# combo_-_no_usb_-_pth_-_tcrt5000.net
KiCad netlist of a schematic drawn in EAGLE
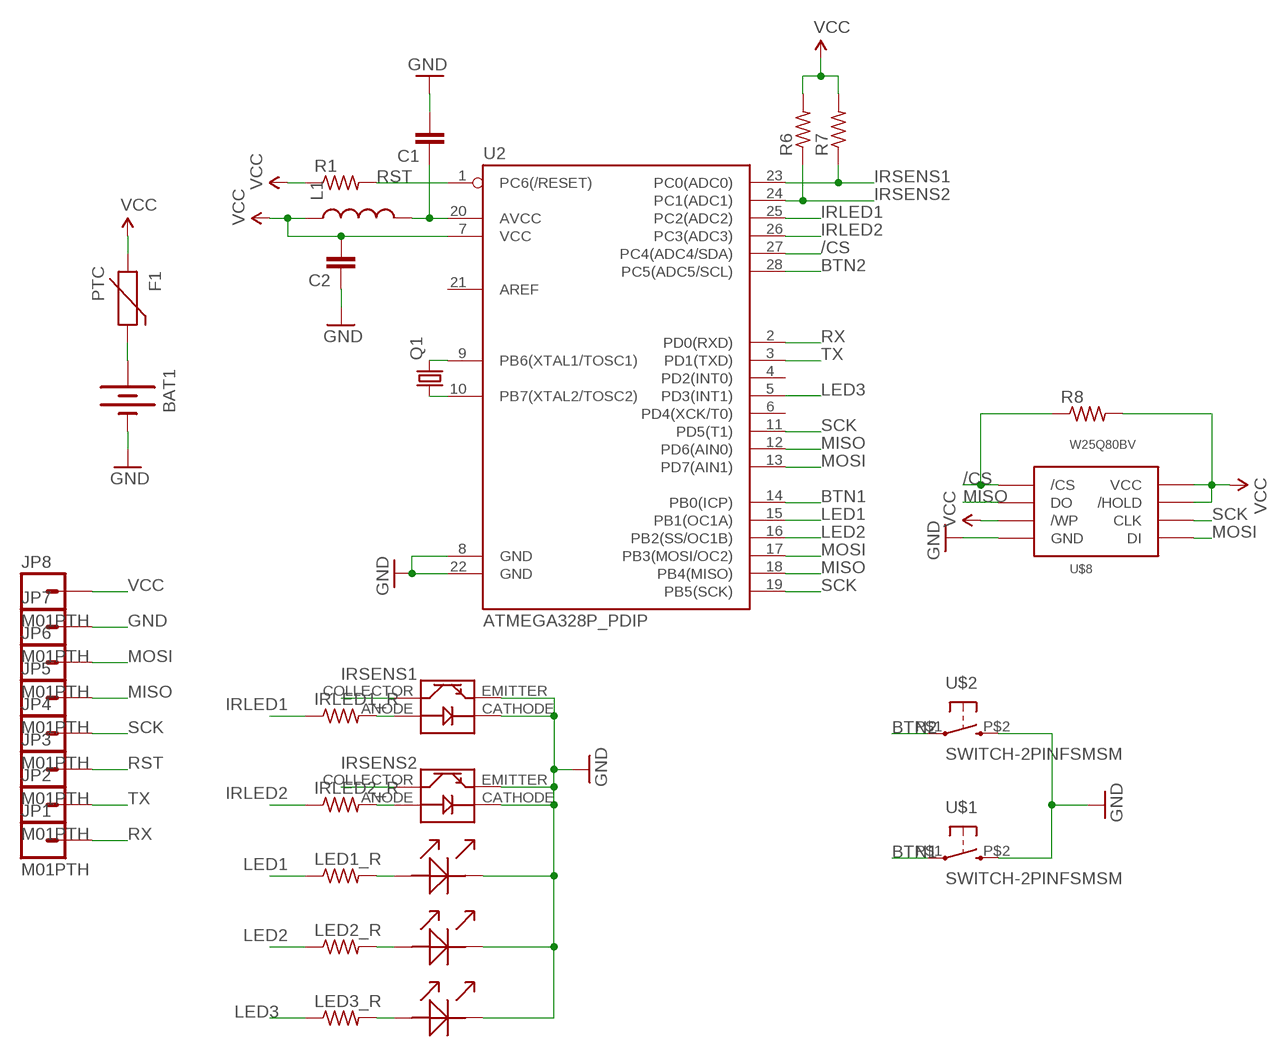
[diagram p0: schematic, sheet 1]

(export (version "E")
  (design (tool "Eeschema 10.0.6"))
  (components
    (comp (ref "BAT1")
      (value "BATTERYBA2032SM")
      (footprint "eagle-import:BA2032SM")
      (libsource (lib "eagle-import") (part "BATTERYBA2032SM"))
    )
    (comp (ref "C1")
      (value "CAP0805")
      (footprint "eagle-import:0805")
      (libsource (lib "eagle-import") (part "CAP0805"))
    )
    (comp (ref "C2")
      (value "CAP0805")
      (footprint "eagle-import:0805")
      (libsource (lib "eagle-import") (part "CAP0805"))
    )
    (comp (ref "F1")
      (value "PTC")
      (footprint "eagle-import:R0805")
      (libsource (lib "eagle-import") (part "PTC"))
    )
    (comp (ref "IRLED1_R")
      (value "R-US_M0805")
      (footprint "eagle-import:M0805")
      (libsource (lib "eagle-import") (part "R-US_M0805"))
    )
    (comp (ref "IRLED2_R")
      (value "R-US_M0805")
      (footprint "eagle-import:M0805")
      (libsource (lib "eagle-import") (part "R-US_M0805"))
    )
    (comp (ref "JP1")
      (value "M01PTH")
      (footprint "eagle-import:1X01")
      (libsource (lib "eagle-import") (part "M01PTH"))
    )
    (comp (ref "JP2")
      (value "M01PTH")
      (footprint "eagle-import:1X01")
      (libsource (lib "eagle-import") (part "M01PTH"))
    )
    (comp (ref "JP3")
      (value "M01PTH")
      (footprint "eagle-import:1X01")
      (libsource (lib "eagle-import") (part "M01PTH"))
    )
    (comp (ref "JP4")
      (value "M01PTH")
      (footprint "eagle-import:1X01")
      (libsource (lib "eagle-import") (part "M01PTH"))
    )
    (comp (ref "JP5")
      (value "M01PTH")
      (footprint "eagle-import:1X01")
      (libsource (lib "eagle-import") (part "M01PTH"))
    )
    (comp (ref "JP6")
      (value "M01PTH")
      (footprint "eagle-import:1X01")
      (libsource (lib "eagle-import") (part "M01PTH"))
    )
    (comp (ref "JP7")
      (value "M01PTH")
      (footprint "eagle-import:1X01")
      (libsource (lib "eagle-import") (part "M01PTH"))
    )
    (comp (ref "JP8")
      (value "M01PTH")
      (footprint "eagle-import:1X01")
      (libsource (lib "eagle-import") (part "M01PTH"))
    )
    (comp (ref "L1")
      (value "INDUCTOR0805")
      (footprint "eagle-import:0805")
      (libsource (lib "eagle-import") (part "INDUCTOR0805"))
    )
    (comp (ref "LED1_R")
      (value "R-US_M0805")
      (footprint "eagle-import:M0805")
      (libsource (lib "eagle-import") (part "R-US_M0805"))
    )
    (comp (ref "LED2_R")
      (value "R-US_M0805")
      (footprint "eagle-import:M0805")
      (libsource (lib "eagle-import") (part "R-US_M0805"))
    )
    (comp (ref "LED3_R")
      (value "R-US_M0805")
      (footprint "eagle-import:M0805")
      (libsource (lib "eagle-import") (part "R-US_M0805"))
    )
    (comp (ref "Q1")
      (value "CRYSTALTC26V")
      (footprint "eagle-import:TC26V")
      (libsource (lib "eagle-import") (part "CRYSTALTC26V"))
    )
    (comp (ref "R1")
      (value "R-US_M0805")
      (footprint "eagle-import:M0805")
      (libsource (lib "eagle-import") (part "R-US_M0805"))
    )
    (comp (ref "R6")
      (value "R-US_M0805")
      (footprint "eagle-import:M0805")
      (libsource (lib "eagle-import") (part "R-US_M0805"))
    )
    (comp (ref "R7")
      (value "R-US_M0805")
      (footprint "eagle-import:M0805")
      (libsource (lib "eagle-import") (part "R-US_M0805"))
    )
    (comp (ref "R8")
      (value "R-US_M0805")
      (footprint "eagle-import:M0805")
      (libsource (lib "eagle-import") (part "R-US_M0805"))
    )
    (comp (ref "U$1")
      (value "SWITCH-2PINFSMSM")
      (footprint "eagle-import:FSMSM-BUTTON")
      (libsource (lib "eagle-import") (part "SWITCH-2PINFSMSM"))
    )
    (comp (ref "U$2")
      (value "SWITCH-2PINFSMSM")
      (footprint "eagle-import:FSMSM-BUTTON")
      (libsource (lib "eagle-import") (part "SWITCH-2PINFSMSM"))
    )
    (comp (ref "U$3")
      (value "IR_SENSORTCRT5000")
      (footprint "eagle-import:TCRT5000")
      (libsource (lib "eagle-import") (part "IR_SENSORTCRT5000"))
    )
    (comp (ref "U$4")
      (value "IR_SENSORTCRT5000")
      (footprint "eagle-import:TCRT5000")
      (libsource (lib "eagle-import") (part "IR_SENSORTCRT5000"))
    )
    (comp (ref "U$5")
      (value "LEDPTH")
      (footprint "eagle-import:LED")
      (libsource (lib "eagle-import") (part "LEDPTH"))
    )
    (comp (ref "U$6")
      (value "LEDPTH")
      (footprint "eagle-import:LED")
      (libsource (lib "eagle-import") (part "LEDPTH"))
    )
    (comp (ref "U$7")
      (value "LED0603")
      (footprint "eagle-import:0603")
      (libsource (lib "eagle-import") (part "LED0603"))
    )
    (comp (ref "U$8")
      (value "W25Q80BVSOIC-08")
      (footprint "eagle-import:W25Q80BV-SOIC-208MIL")
      (libsource (lib "eagle-import") (part "W25Q80BVSOIC-08"))
    )
    (comp (ref "U2")
      (value "ATMEGA328P_PDIP")
      (footprint "eagle-import:DIL28-3")
      (libsource (lib "eagle-import") (part "ATMEGA328P_PDIP"))
    )
  )
  (nets
    (net (code "1") (name "/BTN1") (class "Default")
      (node (ref "U$1") (pin "P$1") (pinfunction "1_P$1") (pintype "passive"))
      (node (ref "U2") (pin "14") (pinfunction "PB0(ICP)_14") (pintype "bidirectional"))
    )
    (net (code "2") (name "/BTN2") (class "Default")
      (node (ref "U$2") (pin "P$1") (pinfunction "1_P$1") (pintype "passive"))
      (node (ref "U2") (pin "28") (pinfunction "PC5(ADC5/SCL)_28") (pintype "bidirectional"))
    )
    (net (code "3") (name "/IRLED1") (class "Default")
      (node (ref "IRLED1_R") (pin "1") (pinfunction "1_1") (pintype "passive"))
      (node (ref "U2") (pin "25") (pinfunction "PC2(ADC2)_25") (pintype "bidirectional"))
    )
    (net (code "4") (name "/IRLED2") (class "Default")
      (node (ref "IRLED2_R") (pin "1") (pinfunction "1_1") (pintype "passive"))
      (node (ref "U2") (pin "26") (pinfunction "PC3(ADC3)_26") (pintype "bidirectional"))
    )
    (net (code "5") (name "/IRSENS1") (class "Default")
      (node (ref "R7") (pin "1") (pinfunction "1_1") (pintype "passive"))
      (node (ref "U$3") (pin "COLLECTOR") (pinfunction "COLLECTOR_COLLECTOR") (pintype "input"))
      (node (ref "U2") (pin "23") (pinfunction "PC0(ADC0)_23") (pintype "bidirectional"))
    )
    (net (code "6") (name "/IRSENS2") (class "Default")
      (node (ref "R6") (pin "1") (pinfunction "1_1") (pintype "passive"))
      (node (ref "U$4") (pin "COLLECTOR") (pinfunction "COLLECTOR_COLLECTOR") (pintype "input"))
      (node (ref "U2") (pin "24") (pinfunction "PC1(ADC1)_24") (pintype "bidirectional"))
    )
    (net (code "7") (name "/LED1") (class "Default")
      (node (ref "LED1_R") (pin "1") (pinfunction "1_1") (pintype "passive"))
      (node (ref "U2") (pin "15") (pinfunction "PB1(OC1A)_15") (pintype "bidirectional"))
    )
    (net (code "8") (name "/LED2") (class "Default")
      (node (ref "LED2_R") (pin "1") (pinfunction "1_1") (pintype "passive"))
      (node (ref "U2") (pin "16") (pinfunction "PB2(SS/OC1B)_16") (pintype "bidirectional"))
    )
    (net (code "9") (name "/LED3") (class "Default")
      (node (ref "LED3_R") (pin "1") (pinfunction "1_1") (pintype "passive"))
      (node (ref "U2") (pin "5") (pinfunction "PD3(INT1)_5") (pintype "bidirectional"))
    )
    (net (code "10") (name "/MISO") (class "Default")
      (node (ref "JP5") (pin "1") (pinfunction "1_1") (pintype "passive"))
      (node (ref "U$8") (pin "DO") (pinfunction "DO_DO") (pintype "bidirectional"))
      (node (ref "U2") (pin "12") (pinfunction "PD6(AIN0)_12") (pintype "bidirectional"))
      (node (ref "U2") (pin "18") (pinfunction "PB4(MISO)_18") (pintype "bidirectional"))
    )
    (net (code "11") (name "/MOSI") (class "Default")
      (node (ref "JP6") (pin "1") (pinfunction "1_1") (pintype "passive"))
      (node (ref "U$8") (pin "DI") (pinfunction "DI_DI") (pintype "bidirectional"))
      (node (ref "U2") (pin "13") (pinfunction "PD7(AIN1)_13") (pintype "bidirectional"))
      (node (ref "U2") (pin "17") (pinfunction "PB3(MOSI/OC2)_17") (pintype "bidirectional"))
    )
    (net (code "12") (name "/RST") (class "Default")
      (node (ref "JP3") (pin "1") (pinfunction "1_1") (pintype "passive"))
      (node (ref "R1") (pin "2") (pinfunction "2_2") (pintype "passive"))
      (node (ref "U2") (pin "1") (pinfunction "PC6(/RESET)_1") (pintype "bidirectional"))
    )
    (net (code "13") (name "/RX") (class "Default")
      (node (ref "JP1") (pin "1") (pinfunction "1_1") (pintype "passive"))
      (node (ref "U2") (pin "2") (pinfunction "PD0(RXD)_2") (pintype "bidirectional"))
    )
    (net (code "14") (name "/SCK") (class "Default")
      (node (ref "JP4") (pin "1") (pinfunction "1_1") (pintype "passive"))
      (node (ref "U$8") (pin "CLK") (pinfunction "CLK_CLK") (pintype "input"))
      (node (ref "U2") (pin "11") (pinfunction "PD5(T1)_11") (pintype "bidirectional"))
      (node (ref "U2") (pin "19") (pinfunction "PB5(SCK)_19") (pintype "bidirectional"))
    )
    (net (code "15") (name "/TX") (class "Default")
      (node (ref "JP2") (pin "1") (pinfunction "1_1") (pintype "passive"))
      (node (ref "U2") (pin "3") (pinfunction "PD1(TXD)_3") (pintype "bidirectional"))
    )
    (net (code "16") (name "/{slash}CS") (class "Default")
      (node (ref "R8") (pin "1") (pinfunction "1_1") (pintype "passive"))
      (node (ref "U$8") (pin "/CS") (pinfunction "/CS_/CS") (pintype "input"))
      (node (ref "U2") (pin "27") (pinfunction "PC4(ADC4/SDA)_27") (pintype "bidirectional"))
    )
    (net (code "17") (name "GND") (class "Default")
      (node (ref "BAT1") (pin "-") (pinfunction "-_-") (pintype "power_in"))
      (node (ref "C1") (pin "2") (pinfunction "2_2") (pintype "passive"))
      (node (ref "C2") (pin "1") (pinfunction "1_1") (pintype "passive"))
      (node (ref "JP7") (pin "1") (pinfunction "1_1") (pintype "passive"))
      (node (ref "U$1") (pin "P$2") (pinfunction "3_P$2") (pintype "passive"))
      (node (ref "U$2") (pin "P$2") (pinfunction "3_P$2") (pintype "passive"))
      (node (ref "U$3") (pin "CATHODE") (pinfunction "LED-_CATHODE") (pintype "input"))
      (node (ref "U$3") (pin "EMITTER") (pinfunction "EMITTER_EMITTER") (pintype "input"))
      (node (ref "U$4") (pin "CATHODE") (pinfunction "LED-_CATHODE") (pintype "input"))
      (node (ref "U$4") (pin "EMITTER") (pinfunction "EMITTER_EMITTER") (pintype "input"))
      (node (ref "U$5") (pin "-") (pinfunction "-_-") (pintype "bidirectional"))
      (node (ref "U$6") (pin "-") (pinfunction "-_-") (pintype "bidirectional"))
      (node (ref "U$7") (pin "2") (pinfunction "-_2") (pintype "bidirectional"))
      (node (ref "U$8") (pin "GND") (pinfunction "GND_GND") (pintype "power_in"))
      (node (ref "U2") (pin "22") (pinfunction "GND_22") (pintype "bidirectional"))
      (node (ref "U2") (pin "8") (pinfunction "GND_8") (pintype "bidirectional"))
    )
    (net (code "18") (name "Net-(BAT1-Pad+)") (class "Default")
      (node (ref "BAT1") (pin "+") (pinfunction "+_+") (pintype "power_in"))
      (node (ref "F1") (pin "2") (pinfunction "2_2") (pintype "bidirectional"))
    )
    (net (code "19") (name "Net-(LED1_R-Pad2)") (class "Default")
      (node (ref "LED1_R") (pin "2") (pinfunction "2_2") (pintype "passive"))
      (node (ref "U$5") (pin "+") (pinfunction "+_+") (pintype "bidirectional"))
    )
    (net (code "20") (name "Net-(LED2_R-Pad2)") (class "Default")
      (node (ref "LED2_R") (pin "2") (pinfunction "2_2") (pintype "passive"))
      (node (ref "U$6") (pin "+") (pinfunction "+_+") (pintype "bidirectional"))
    )
    (net (code "21") (name "Net-(U$3-LED+)") (class "Default")
      (node (ref "IRLED1_R") (pin "2") (pinfunction "2_2") (pintype "passive"))
      (node (ref "U$3") (pin "ANODE") (pinfunction "LED+_ANODE") (pintype "input"))
    )
    (net (code "22") (name "Net-(U$4-LED+)") (class "Default")
      (node (ref "IRLED2_R") (pin "2") (pinfunction "2_2") (pintype "passive"))
      (node (ref "U$4") (pin "ANODE") (pinfunction "LED+_ANODE") (pintype "input"))
    )
    (net (code "23") (name "Net-(U$7-+)") (class "Default")
      (node (ref "LED3_R") (pin "2") (pinfunction "2_2") (pintype "passive"))
      (node (ref "U$7") (pin "1") (pinfunction "+_1") (pintype "bidirectional"))
    )
    (net (code "24") (name "Net-(U2-AVCC)") (class "Default")
      (node (ref "C1") (pin "1") (pinfunction "1_1") (pintype "passive"))
      (node (ref "L1") (pin "2") (pinfunction "2_2") (pintype "passive"))
      (node (ref "U2") (pin "20") (pinfunction "AVCC_20") (pintype "bidirectional"))
    )
    (net (code "25") (name "Net-(U2-PB6(XTAL1{slash}TOSC1))") (class "Default")
      (node (ref "Q1") (pin "2") (pinfunction "2_2") (pintype "passive"))
      (node (ref "U2") (pin "9") (pinfunction "PB6(XTAL1/TOSC1)_9") (pintype "bidirectional"))
    )
    (net (code "26") (name "Net-(U2-PB7(XTAL2{slash}TOSC2))") (class "Default")
      (node (ref "Q1") (pin "1") (pinfunction "1_1") (pintype "passive"))
      (node (ref "U2") (pin "10") (pinfunction "PB7(XTAL2/TOSC2)_10") (pintype "bidirectional"))
    )
    (net (code "27") (name "VCC") (class "Default")
      (node (ref "C2") (pin "2") (pinfunction "2_2") (pintype "passive"))
      (node (ref "F1") (pin "1") (pinfunction "1_1") (pintype "bidirectional"))
      (node (ref "JP8") (pin "1") (pinfunction "1_1") (pintype "passive"))
      (node (ref "L1") (pin "1") (pinfunction "1_1") (pintype "passive"))
      (node (ref "R1") (pin "1") (pinfunction "1_1") (pintype "passive"))
      (node (ref "R6") (pin "2") (pinfunction "2_2") (pintype "passive"))
      (node (ref "R7") (pin "2") (pinfunction "2_2") (pintype "passive"))
      (node (ref "R8") (pin "2") (pinfunction "2_2") (pintype "passive"))
      (node (ref "U$8") (pin "/HOLD") (pinfunction "/HOLD_/HOLD") (pintype "bidirectional"))
      (node (ref "U$8") (pin "/WP") (pinfunction "/WP_/WP") (pintype "bidirectional"))
      (node (ref "U$8") (pin "VCC") (pinfunction "VCC_VCC") (pintype "power_in"))
      (node (ref "U2") (pin "7") (pinfunction "VCC_7") (pintype "bidirectional"))
    )
    (net (code "28") (name "unconnected-(U2-AREF-Pad21)") (class "Default")
      (node (ref "U2") (pin "21") (pinfunction "AREF_21") (pintype "bidirectional"))
    )
    (net (code "29") (name "unconnected-(U2-PD2(INT0)-Pad4)") (class "Default")
      (node (ref "U2") (pin "4") (pinfunction "PD2(INT0)_4") (pintype "bidirectional"))
    )
    (net (code "30") (name "unconnected-(U2-PD4(XCK{slash}T0)-Pad6)") (class "Default")
      (node (ref "U2") (pin "6") (pinfunction "PD4(XCK/T0)_6") (pintype "bidirectional"))
    )
  )
)
